# m6502-prototyping-board.net
KiCad netlist of a schematic drawn in EAGLE
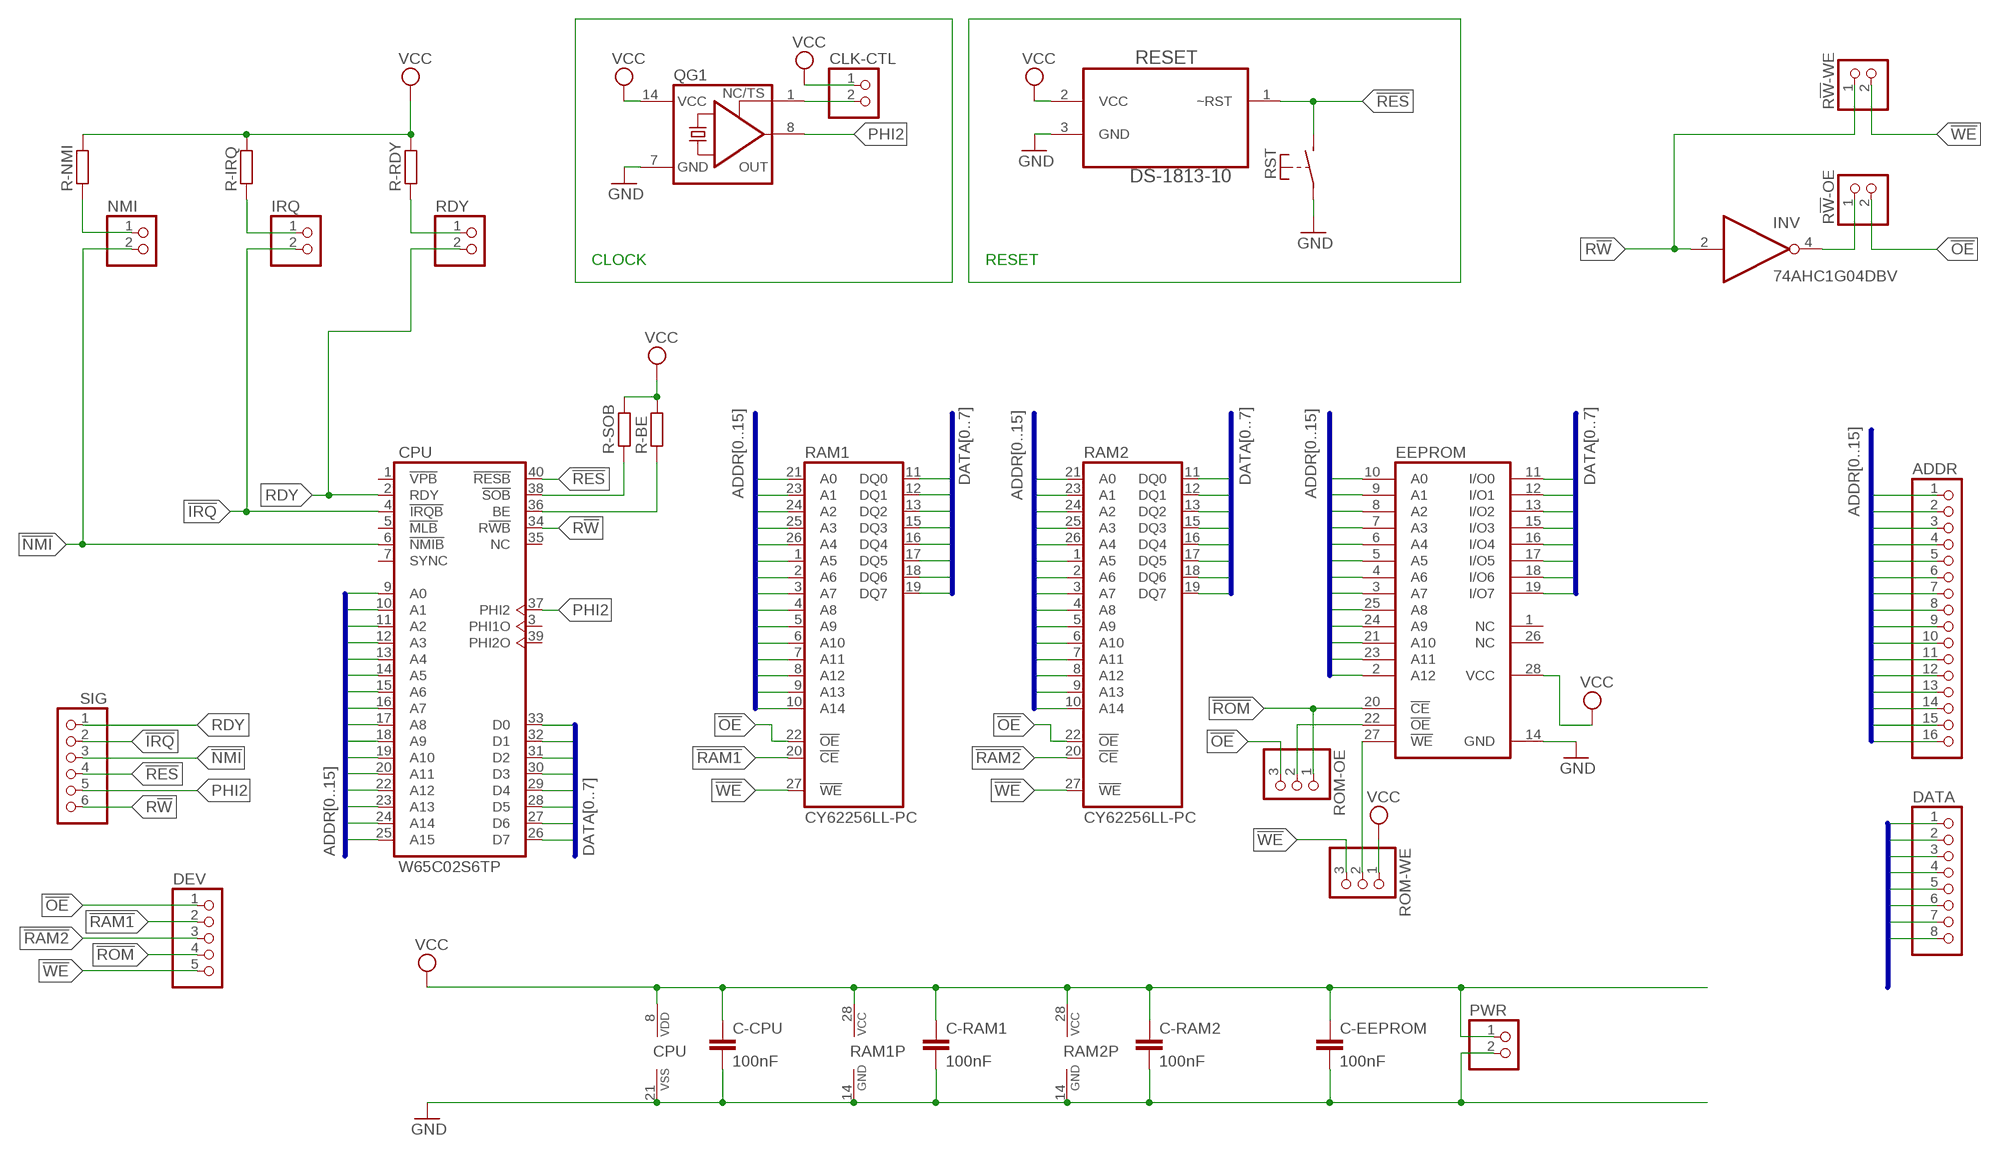
[diagram p0: schematic, sheet 1]

(export (version "E")
  (design (tool "Eeschema 10.0.6"))
  (components
    (comp (ref "ADDR")
      (value "PINHD-1X16")
      (footprint "eagle-import:1X16")
      (libsource (lib "eagle-import") (part "PINHD-1X16"))
    )
    (comp (ref "C-CPU")
      (value "100nF")
      (footprint "eagle-import:C0805")
      (libsource (lib "eagle-import") (part "C-EUC0805"))
    )
    (comp (ref "C-EEPROM")
      (value "100nF")
      (footprint "eagle-import:C0805")
      (libsource (lib "eagle-import") (part "C-EUC0805"))
    )
    (comp (ref "C-RAM1")
      (value "100nF")
      (footprint "eagle-import:C0805")
      (libsource (lib "eagle-import") (part "C-EUC0805"))
    )
    (comp (ref "C-RAM2")
      (value "100nF")
      (footprint "eagle-import:C0805")
      (libsource (lib "eagle-import") (part "C-EUC0805"))
    )
    (comp (ref "CLK-CTL")
      (value "PINHD-1X2")
      (footprint "eagle-import:1X02")
      (libsource (lib "eagle-import") (part "PINHD-1X2"))
    )
    (comp (ref "CPU")
      (value "W65C02S6TP")
      (footprint "eagle-import:DIL40")
      (libsource (lib "eagle-import") (part "W65C02SP6T"))
    )
    (comp (ref "DATA")
      (value "PINHD-1X8")
      (footprint "eagle-import:1X08")
      (libsource (lib "eagle-import") (part "PINHD-1X8"))
    )
    (comp (ref "DEV")
      (value "PINHD-1X5")
      (footprint "eagle-import:1X05")
      (libsource (lib "eagle-import") (part "PINHD-1X5"))
    )
    (comp (ref "EEPROM")
      (value "28C64C")
      (footprint "eagle-import:DIL28-6")
      (fields (field (name "MPN") "AT28C64B-15PU"))
      (libsource (lib "eagle-import") (part "28C64C"))
    )
    (comp (ref "INV")
      (value "74AHC1G04DBV")
      (footprint "eagle-import:SOT23-5")
      (libsource (lib "eagle-import") (part "741G04DBVAHC"))
    )
    (comp (ref "IRQ")
      (value "PINHD-1X2")
      (footprint "eagle-import:1X02")
      (libsource (lib "eagle-import") (part "PINHD-1X2"))
    )
    (comp (ref "NMI")
      (value "PINHD-1X2")
      (footprint "eagle-import:1X02")
      (libsource (lib "eagle-import") (part "PINHD-1X2"))
    )
    (comp (ref "PWR")
      (value "PINHD-1X2")
      (footprint "eagle-import:1X02")
      (libsource (lib "eagle-import") (part "PINHD-1X2"))
    )
    (comp (ref "QG1")
      (value "XO-14")
      (footprint "eagle-import:DIL14S")
      (libsource (lib "eagle-import") (part "XO-14"))
    )
    (comp (ref "R!W!-OE")
      (value "PINHD-1X2")
      (footprint "eagle-import:1X02")
      (libsource (lib "eagle-import") (part "PINHD-1X2"))
    )
    (comp (ref "R!W!-WE")
      (value "PINHD-1X2")
      (footprint "eagle-import:1X02")
      (libsource (lib "eagle-import") (part "PINHD-1X2"))
    )
    (comp (ref "R-BE")
      (value "R-EU_M1206")
      (footprint "eagle-import:M1206")
      (libsource (lib "eagle-import") (part "R-EU_M1206"))
    )
    (comp (ref "R-IRQ")
      (value "R-EU_M1206")
      (footprint "eagle-import:M1206")
      (libsource (lib "eagle-import") (part "R-EU_M1206"))
    )
    (comp (ref "R-NMI")
      (value "R-EU_M1206")
      (footprint "eagle-import:M1206")
      (libsource (lib "eagle-import") (part "R-EU_M1206"))
    )
    (comp (ref "R-RDY")
      (value "R-EU_M1206")
      (footprint "eagle-import:M1206")
      (libsource (lib "eagle-import") (part "R-EU_M1206"))
    )
    (comp (ref "R-SOB")
      (value "R-EU_M1206")
      (footprint "eagle-import:M1206")
      (libsource (lib "eagle-import") (part "R-EU_M1206"))
    )
    (comp (ref "RAM1")
      (value "CY62256LL-PC")
      (footprint "eagle-import:DIL28-6")
      (libsource (lib "eagle-import") (part "CY62256LL-?PC"))
    )
    (comp (ref "RAM2")
      (value "CY62256LL-PC")
      (footprint "eagle-import:DIL28-6")
      (libsource (lib "eagle-import") (part "CY62256LL-?PC"))
    )
    (comp (ref "RDY")
      (value "PINHD-1X2")
      (footprint "eagle-import:1X02")
      (libsource (lib "eagle-import") (part "PINHD-1X2"))
    )
    (comp (ref "RESET")
      (value "DS-1813-10")
      (footprint "eagle-import:TO-92")
      (libsource (lib "eagle-import") (part "DS-1813-10"))
    )
    (comp (ref "ROM-OE")
      (value "PINHD-1X3")
      (footprint "eagle-import:1X03")
      (libsource (lib "eagle-import") (part "PINHD-1X3"))
    )
    (comp (ref "ROM-WE")
      (value "PINHD-1X3")
      (footprint "eagle-import:1X03")
      (libsource (lib "eagle-import") (part "PINHD-1X3"))
    )
    (comp (ref "RST")
      (value "FSM")
      (footprint "eagle-import:FSM")
      (libsource (lib "eagle-import") (part "FSM"))
    )
    (comp (ref "SIG")
      (value "PINHD-1X6")
      (footprint "eagle-import:1X06")
      (libsource (lib "eagle-import") (part "PINHD-1X6"))
    )
  )
  (nets
    (net (code "1") (name "/ADDR0") (class "Default")
      (node (ref "ADDR") (pin "1") (pinfunction "1_1") (pintype "passive"))
      (node (ref "CPU") (pin "9") (pinfunction "A0_9") (pintype "output"))
      (node (ref "EEPROM") (pin "10") (pinfunction "A0_10") (pintype "input"))
      (node (ref "RAM1") (pin "10") (pinfunction "A14_10") (pintype "input"))
      (node (ref "RAM2") (pin "10") (pinfunction "A14_10") (pintype "input"))
    )
    (net (code "2") (name "/ADDR1") (class "Default")
      (node (ref "ADDR") (pin "2") (pinfunction "2_2") (pintype "passive"))
      (node (ref "CPU") (pin "10") (pinfunction "A1_10") (pintype "output"))
      (node (ref "EEPROM") (pin "9") (pinfunction "A1_9") (pintype "input"))
      (node (ref "RAM1") (pin "9") (pinfunction "A13_9") (pintype "input"))
      (node (ref "RAM2") (pin "9") (pinfunction "A13_9") (pintype "input"))
    )
    (net (code "3") (name "/ADDR2") (class "Default")
      (node (ref "ADDR") (pin "3") (pinfunction "3_3") (pintype "passive"))
      (node (ref "CPU") (pin "11") (pinfunction "A2_11") (pintype "output"))
      (node (ref "EEPROM") (pin "8") (pinfunction "A2_8") (pintype "input"))
      (node (ref "RAM1") (pin "8") (pinfunction "A12_8") (pintype "input"))
      (node (ref "RAM2") (pin "8") (pinfunction "A12_8") (pintype "input"))
    )
    (net (code "4") (name "/ADDR3") (class "Default")
      (node (ref "ADDR") (pin "4") (pinfunction "4_4") (pintype "passive"))
      (node (ref "CPU") (pin "12") (pinfunction "A3_12") (pintype "output"))
      (node (ref "EEPROM") (pin "7") (pinfunction "A3_7") (pintype "input"))
      (node (ref "RAM1") (pin "7") (pinfunction "A11_7") (pintype "input"))
      (node (ref "RAM2") (pin "7") (pinfunction "A11_7") (pintype "input"))
    )
    (net (code "5") (name "/ADDR4") (class "Default")
      (node (ref "ADDR") (pin "5") (pinfunction "5_5") (pintype "passive"))
      (node (ref "CPU") (pin "13") (pinfunction "A4_13") (pintype "output"))
      (node (ref "EEPROM") (pin "6") (pinfunction "A4_6") (pintype "input"))
      (node (ref "RAM1") (pin "6") (pinfunction "A10_6") (pintype "input"))
      (node (ref "RAM2") (pin "6") (pinfunction "A10_6") (pintype "input"))
    )
    (net (code "6") (name "/ADDR5") (class "Default")
      (node (ref "ADDR") (pin "6") (pinfunction "6_6") (pintype "passive"))
      (node (ref "CPU") (pin "14") (pinfunction "A5_14") (pintype "output"))
      (node (ref "EEPROM") (pin "5") (pinfunction "A5_5") (pintype "input"))
      (node (ref "RAM1") (pin "5") (pinfunction "A9_5") (pintype "input"))
      (node (ref "RAM2") (pin "5") (pinfunction "A9_5") (pintype "input"))
    )
    (net (code "7") (name "/ADDR6") (class "Default")
      (node (ref "ADDR") (pin "7") (pinfunction "7_7") (pintype "passive"))
      (node (ref "CPU") (pin "15") (pinfunction "A6_15") (pintype "output"))
      (node (ref "EEPROM") (pin "4") (pinfunction "A6_4") (pintype "input"))
      (node (ref "RAM1") (pin "4") (pinfunction "A8_4") (pintype "input"))
      (node (ref "RAM2") (pin "4") (pinfunction "A8_4") (pintype "input"))
    )
    (net (code "8") (name "/ADDR7") (class "Default")
      (node (ref "ADDR") (pin "8") (pinfunction "8_8") (pintype "passive"))
      (node (ref "CPU") (pin "16") (pinfunction "A7_16") (pintype "output"))
      (node (ref "EEPROM") (pin "3") (pinfunction "A7_3") (pintype "input"))
      (node (ref "RAM1") (pin "3") (pinfunction "A7_3") (pintype "input"))
      (node (ref "RAM2") (pin "3") (pinfunction "A7_3") (pintype "input"))
    )
    (net (code "9") (name "/ADDR8") (class "Default")
      (node (ref "ADDR") (pin "9") (pinfunction "9_9") (pintype "passive"))
      (node (ref "CPU") (pin "17") (pinfunction "A8_17") (pintype "output"))
      (node (ref "EEPROM") (pin "25") (pinfunction "A8_25") (pintype "input"))
      (node (ref "RAM1") (pin "25") (pinfunction "A3_25") (pintype "input"))
      (node (ref "RAM2") (pin "25") (pinfunction "A3_25") (pintype "input"))
    )
    (net (code "10") (name "/ADDR9") (class "Default")
      (node (ref "ADDR") (pin "10") (pinfunction "10_10") (pintype "passive"))
      (node (ref "CPU") (pin "18") (pinfunction "A9_18") (pintype "output"))
      (node (ref "EEPROM") (pin "24") (pinfunction "A9_24") (pintype "input"))
      (node (ref "RAM1") (pin "24") (pinfunction "A2_24") (pintype "input"))
      (node (ref "RAM2") (pin "24") (pinfunction "A2_24") (pintype "input"))
    )
    (net (code "11") (name "/ADDR10") (class "Default")
      (node (ref "ADDR") (pin "11") (pinfunction "11_11") (pintype "passive"))
      (node (ref "CPU") (pin "19") (pinfunction "A10_19") (pintype "output"))
      (node (ref "EEPROM") (pin "21") (pinfunction "A10_21") (pintype "input"))
      (node (ref "RAM1") (pin "21") (pinfunction "A0_21") (pintype "input"))
      (node (ref "RAM2") (pin "21") (pinfunction "A0_21") (pintype "input"))
    )
    (net (code "12") (name "/ADDR11") (class "Default")
      (node (ref "ADDR") (pin "12") (pinfunction "12_12") (pintype "passive"))
      (node (ref "CPU") (pin "20") (pinfunction "A11_20") (pintype "output"))
      (node (ref "EEPROM") (pin "23") (pinfunction "A11_23") (pintype "input"))
      (node (ref "RAM1") (pin "23") (pinfunction "A1_23") (pintype "input"))
      (node (ref "RAM2") (pin "23") (pinfunction "A1_23") (pintype "input"))
    )
    (net (code "13") (name "/ADDR12") (class "Default")
      (node (ref "ADDR") (pin "13") (pinfunction "13_13") (pintype "passive"))
      (node (ref "CPU") (pin "22") (pinfunction "A12_22") (pintype "output"))
      (node (ref "EEPROM") (pin "2") (pinfunction "A12_2") (pintype "input"))
      (node (ref "RAM1") (pin "2") (pinfunction "A6_2") (pintype "input"))
      (node (ref "RAM2") (pin "2") (pinfunction "A6_2") (pintype "input"))
    )
    (net (code "14") (name "/ADDR13") (class "Default")
      (node (ref "ADDR") (pin "14") (pinfunction "14_14") (pintype "passive"))
      (node (ref "CPU") (pin "23") (pinfunction "A13_23") (pintype "output"))
      (node (ref "RAM1") (pin "26") (pinfunction "A4_26") (pintype "input"))
      (node (ref "RAM2") (pin "26") (pinfunction "A4_26") (pintype "input"))
    )
    (net (code "15") (name "/ADDR14") (class "Default")
      (node (ref "ADDR") (pin "15") (pinfunction "15_15") (pintype "passive"))
      (node (ref "CPU") (pin "24") (pinfunction "A14_24") (pintype "output"))
      (node (ref "RAM1") (pin "1") (pinfunction "A5_1") (pintype "input"))
      (node (ref "RAM2") (pin "1") (pinfunction "A5_1") (pintype "input"))
    )
    (net (code "16") (name "/ADDR15") (class "Default")
      (node (ref "ADDR") (pin "16") (pinfunction "16_16") (pintype "passive"))
      (node (ref "CPU") (pin "25") (pinfunction "A15_25") (pintype "output"))
    )
    (net (code "18") (name "/DATA0") (class "Default")
      (node (ref "CPU") (pin "33") (pinfunction "D0_33") (pintype "bidirectional"))
      (node (ref "DATA") (pin "1") (pinfunction "1_1") (pintype "passive"))
      (node (ref "EEPROM") (pin "11") (pinfunction "I/O0_11") (pintype "bidirectional"))
      (node (ref "RAM1") (pin "11") (pinfunction "DQ0_11") (pintype "bidirectional"))
      (node (ref "RAM2") (pin "11") (pinfunction "DQ0_11") (pintype "bidirectional"))
    )
    (net (code "19") (name "/DATA1") (class "Default")
      (node (ref "CPU") (pin "32") (pinfunction "D1_32") (pintype "bidirectional"))
      (node (ref "DATA") (pin "2") (pinfunction "2_2") (pintype "passive"))
      (node (ref "EEPROM") (pin "12") (pinfunction "I/O1_12") (pintype "bidirectional"))
      (node (ref "RAM1") (pin "12") (pinfunction "DQ1_12") (pintype "bidirectional"))
      (node (ref "RAM2") (pin "12") (pinfunction "DQ1_12") (pintype "bidirectional"))
    )
    (net (code "20") (name "/DATA2") (class "Default")
      (node (ref "CPU") (pin "31") (pinfunction "D2_31") (pintype "bidirectional"))
      (node (ref "DATA") (pin "3") (pinfunction "3_3") (pintype "passive"))
      (node (ref "EEPROM") (pin "13") (pinfunction "I/O2_13") (pintype "bidirectional"))
      (node (ref "RAM1") (pin "13") (pinfunction "DQ2_13") (pintype "bidirectional"))
      (node (ref "RAM2") (pin "13") (pinfunction "DQ2_13") (pintype "bidirectional"))
    )
    (net (code "21") (name "/DATA3") (class "Default")
      (node (ref "CPU") (pin "30") (pinfunction "D3_30") (pintype "bidirectional"))
      (node (ref "DATA") (pin "4") (pinfunction "4_4") (pintype "passive"))
      (node (ref "EEPROM") (pin "15") (pinfunction "I/O3_15") (pintype "bidirectional"))
      (node (ref "RAM1") (pin "15") (pinfunction "DQ3_15") (pintype "bidirectional"))
      (node (ref "RAM2") (pin "15") (pinfunction "DQ3_15") (pintype "bidirectional"))
    )
    (net (code "22") (name "/DATA4") (class "Default")
      (node (ref "CPU") (pin "29") (pinfunction "D4_29") (pintype "bidirectional"))
      (node (ref "DATA") (pin "5") (pinfunction "5_5") (pintype "passive"))
      (node (ref "EEPROM") (pin "16") (pinfunction "I/O4_16") (pintype "bidirectional"))
      (node (ref "RAM1") (pin "16") (pinfunction "DQ4_16") (pintype "bidirectional"))
      (node (ref "RAM2") (pin "16") (pinfunction "DQ4_16") (pintype "bidirectional"))
    )
    (net (code "23") (name "/DATA5") (class "Default")
      (node (ref "CPU") (pin "28") (pinfunction "D5_28") (pintype "bidirectional"))
      (node (ref "DATA") (pin "6") (pinfunction "6_6") (pintype "passive"))
      (node (ref "EEPROM") (pin "17") (pinfunction "I/O5_17") (pintype "bidirectional"))
      (node (ref "RAM1") (pin "17") (pinfunction "DQ5_17") (pintype "bidirectional"))
      (node (ref "RAM2") (pin "17") (pinfunction "DQ5_17") (pintype "bidirectional"))
    )
    (net (code "24") (name "/DATA6") (class "Default")
      (node (ref "CPU") (pin "27") (pinfunction "D6_27") (pintype "bidirectional"))
      (node (ref "DATA") (pin "7") (pinfunction "7_7") (pintype "passive"))
      (node (ref "EEPROM") (pin "18") (pinfunction "I/O6_18") (pintype "bidirectional"))
      (node (ref "RAM1") (pin "18") (pinfunction "DQ6_18") (pintype "bidirectional"))
      (node (ref "RAM2") (pin "18") (pinfunction "DQ6_18") (pintype "bidirectional"))
    )
    (net (code "25") (name "/DATA7") (class "Default")
      (node (ref "CPU") (pin "26") (pinfunction "D7_26") (pintype "bidirectional"))
      (node (ref "DATA") (pin "8") (pinfunction "8_8") (pintype "passive"))
      (node (ref "EEPROM") (pin "19") (pinfunction "I/O7_19") (pintype "bidirectional"))
      (node (ref "RAM1") (pin "19") (pinfunction "DQ7_19") (pintype "bidirectional"))
      (node (ref "RAM2") (pin "19") (pinfunction "DQ7_19") (pintype "bidirectional"))
    )
    (net (code "27") (name "/R~{W}") (class "Default")
      (node (ref "CPU") (pin "34") (pinfunction "R~{WB}_34") (pintype "output"))
      (node (ref "INV") (pin "2") (pinfunction "I_2") (pintype "input"))
      (node (ref "R!W!-WE") (pin "1") (pinfunction "1_1") (pintype "passive"))
      (node (ref "SIG") (pin "6") (pinfunction "6_6") (pintype "passive"))
    )
    (net (code "28") (name "/~{IRQ}") (class "Default")
      (node (ref "CPU") (pin "4") (pinfunction "~{IRQB}_4") (pintype "input"))
      (node (ref "IRQ") (pin "2") (pinfunction "2_2") (pintype "passive"))
      (node (ref "SIG") (pin "2") (pinfunction "2_2") (pintype "passive"))
    )
    (net (code "29") (name "/~{NMI}") (class "Default")
      (node (ref "CPU") (pin "6") (pinfunction "~{NMIB}_6") (pintype "input"))
      (node (ref "NMI") (pin "2") (pinfunction "2_2") (pintype "passive"))
      (node (ref "SIG") (pin "3") (pinfunction "3_3") (pintype "passive"))
    )
    (net (code "30") (name "/~{OE}") (class "Default")
      (node (ref "DEV") (pin "1") (pinfunction "1_1") (pintype "passive"))
      (node (ref "R!W!-OE") (pin "2") (pinfunction "2_2") (pintype "passive"))
      (node (ref "RAM1") (pin "22") (pinfunction "~{OE}_22") (pintype "input"))
      (node (ref "RAM2") (pin "22") (pinfunction "~{OE}_22") (pintype "input"))
      (node (ref "ROM-OE") (pin "3") (pinfunction "3_3") (pintype "passive"))
    )
    (net (code "31") (name "/~{RAM1}") (class "Default")
      (node (ref "DEV") (pin "2") (pinfunction "2_2") (pintype "passive"))
      (node (ref "RAM1") (pin "20") (pinfunction "~{CE}_20") (pintype "input"))
    )
    (net (code "32") (name "/~{RAM2}") (class "Default")
      (node (ref "DEV") (pin "3") (pinfunction "3_3") (pintype "passive"))
      (node (ref "RAM2") (pin "20") (pinfunction "~{CE}_20") (pintype "input"))
    )
    (net (code "33") (name "/~{RES}") (class "Default")
      (node (ref "CPU") (pin "40") (pinfunction "~{RESB}_40") (pintype "input"))
      (node (ref "RESET") (pin "1") (pinfunction "~{RST}_1") (pintype "output"))
      (node (ref "RST") (pin "P$2") (pinfunction "S_P$2") (pintype "passive"))
      (node (ref "SIG") (pin "4") (pinfunction "4_4") (pintype "passive"))
    )
    (net (code "34") (name "/~{ROM}") (class "Default")
      (node (ref "DEV") (pin "4") (pinfunction "4_4") (pintype "passive"))
      (node (ref "EEPROM") (pin "20") (pinfunction "~{CE}_20") (pintype "input"))
      (node (ref "ROM-OE") (pin "1") (pinfunction "1_1") (pintype "passive"))
    )
    (net (code "35") (name "/~{WE}") (class "Default")
      (node (ref "DEV") (pin "5") (pinfunction "5_5") (pintype "passive"))
      (node (ref "R!W!-WE") (pin "2") (pinfunction "2_2") (pintype "passive"))
      (node (ref "RAM1") (pin "27") (pinfunction "~{WE}_27") (pintype "input"))
      (node (ref "RAM2") (pin "27") (pinfunction "~{WE}_27") (pintype "input"))
      (node (ref "ROM-WE") (pin "3") (pinfunction "3_3") (pintype "passive"))
    )
    (net (code "36") (name "GND") (class "Default")
      (node (ref "C-CPU") (pin "2") (pinfunction "2_2") (pintype "passive"))
      (node (ref "C-EEPROM") (pin "2") (pinfunction "2_2") (pintype "passive"))
      (node (ref "C-RAM1") (pin "2") (pinfunction "2_2") (pintype "passive"))
      (node (ref "C-RAM2") (pin "2") (pinfunction "2_2") (pintype "passive"))
      (node (ref "CPU") (pin "21") (pinfunction "VSS_21") (pintype "power_in"))
      (node (ref "EEPROM") (pin "14") (pinfunction "GND_14") (pintype "power_in"))
      (node (ref "PWR") (pin "2") (pinfunction "2_2") (pintype "passive"))
      (node (ref "QG1") (pin "7") (pinfunction "GND_7") (pintype "power_in"))
      (node (ref "RAM1") (pin "14") (pinfunction "GND_14") (pintype "power_in"))
      (node (ref "RAM2") (pin "14") (pinfunction "GND_14") (pintype "power_in"))
      (node (ref "RESET") (pin "3") (pinfunction "GND_3") (pintype "passive"))
      (node (ref "RST") (pin "P$1") (pinfunction "P_P$1") (pintype "passive"))
    )
    (net (code "37") (name "Net-(CPUA-BE)") (class "Default")
      (node (ref "CPU") (pin "36") (pinfunction "BE_36") (pintype "input"))
      (node (ref "R-BE") (pin "1") (pinfunction "1_1") (pintype "passive"))
    )
    (net (code "38") (name "Net-(CPUA-~{SOB})") (class "Default")
      (node (ref "CPU") (pin "38") (pinfunction "~{SOB}_38") (pintype "input"))
      (node (ref "R-SOB") (pin "1") (pinfunction "1_1") (pintype "passive"))
    )
    (net (code "39") (name "Net-(EEPROM-~{OE})") (class "Default")
      (node (ref "EEPROM") (pin "22") (pinfunction "~{OE}_22") (pintype "input"))
      (node (ref "ROM-OE") (pin "2") (pinfunction "2_2") (pintype "passive"))
    )
    (net (code "40") (name "Net-(EEPROM-~{WE})") (class "Default")
      (node (ref "EEPROM") (pin "27") (pinfunction "~{WE}_27") (pintype "input"))
      (node (ref "ROM-WE") (pin "2") (pinfunction "2_2") (pintype "passive"))
    )
    (net (code "41") (name "Net-(INVA-O)") (class "Default")
      (node (ref "INV") (pin "4") (pinfunction "O_4") (pintype "output"))
      (node (ref "R!W!-OE") (pin "1") (pinfunction "1_1") (pintype "passive"))
    )
    (net (code "42") (name "Net-(IRQ-Pad1)") (class "Default")
      (node (ref "IRQ") (pin "1") (pinfunction "1_1") (pintype "passive"))
      (node (ref "R-IRQ") (pin "1") (pinfunction "1_1") (pintype "passive"))
    )
    (net (code "43") (name "Net-(NMI-Pad1)") (class "Default")
      (node (ref "NMI") (pin "1") (pinfunction "1_1") (pintype "passive"))
      (node (ref "R-NMI") (pin "1") (pinfunction "1_1") (pintype "passive"))
    )
    (net (code "44") (name "Net-(QG1-TS)") (class "Default")
      (node (ref "CLK-CTL") (pin "2") (pinfunction "2_2") (pintype "passive"))
      (node (ref "QG1") (pin "1") (pinfunction "TS_1") (pintype "passive"))
    )
    (net (code "45") (name "Net-(R-RDY-Pad1)") (class "Default")
      (node (ref "R-RDY") (pin "1") (pinfunction "1_1") (pintype "passive"))
      (node (ref "RDY") (pin "1") (pinfunction "1_1") (pintype "passive"))
    )
    (net (code "46") (name "PHI2") (class "Default")
      (node (ref "CPU") (pin "37") (pinfunction "PHI2_37") (pintype "input"))
      (node (ref "QG1") (pin "8") (pinfunction "OUT_8") (pintype "output"))
      (node (ref "SIG") (pin "5") (pinfunction "5_5") (pintype "passive"))
    )
    (net (code "47") (name "RDY") (class "Default")
      (node (ref "CPU") (pin "2") (pinfunction "RDY_2") (pintype "input"))
      (node (ref "RDY") (pin "2") (pinfunction "2_2") (pintype "passive"))
      (node (ref "SIG") (pin "1") (pinfunction "1_1") (pintype "passive"))
    )
    (net (code "48") (name "VCC") (class "Default")
      (node (ref "C-CPU") (pin "1") (pinfunction "1_1") (pintype "passive"))
      (node (ref "C-EEPROM") (pin "1") (pinfunction "1_1") (pintype "passive"))
      (node (ref "C-RAM1") (pin "1") (pinfunction "1_1") (pintype "passive"))
      (node (ref "C-RAM2") (pin "1") (pinfunction "1_1") (pintype "passive"))
      (node (ref "CLK-CTL") (pin "1") (pinfunction "1_1") (pintype "passive"))
      (node (ref "CPU") (pin "8") (pinfunction "VDD_8") (pintype "power_in"))
      (node (ref "EEPROM") (pin "28") (pinfunction "VCC_28") (pintype "power_in"))
      (node (ref "PWR") (pin "1") (pinfunction "1_1") (pintype "passive"))
      (node (ref "QG1") (pin "14") (pinfunction "VCC_14") (pintype "power_in"))
      (node (ref "R-BE") (pin "2") (pinfunction "2_2") (pintype "passive"))
      (node (ref "R-IRQ") (pin "2") (pinfunction "2_2") (pintype "passive"))
      (node (ref "R-NMI") (pin "2") (pinfunction "2_2") (pintype "passive"))
      (node (ref "R-RDY") (pin "2") (pinfunction "2_2") (pintype "passive"))
      (node (ref "R-SOB") (pin "2") (pinfunction "2_2") (pintype "passive"))
      (node (ref "RAM1") (pin "28") (pinfunction "VCC_28") (pintype "power_in"))
      (node (ref "RAM2") (pin "28") (pinfunction "VCC_28") (pintype "power_in"))
      (node (ref "RESET") (pin "2") (pinfunction "VCC_2") (pintype "power_in"))
      (node (ref "ROM-WE") (pin "1") (pinfunction "1_1") (pintype "passive"))
    )
    (net (code "49") (name "unconnected-(CPUA-NC-Pad35)") (class "Default")
      (node (ref "CPU") (pin "35") (pinfunction "NC_35") (pintype "no_connect"))
    )
    (net (code "50") (name "unconnected-(CPUA-PHI1O-Pad3)") (class "Default")
      (node (ref "CPU") (pin "3") (pinfunction "PHI1O_3") (pintype "output"))
    )
    (net (code "51") (name "unconnected-(CPUA-PHI2O-Pad39)") (class "Default")
      (node (ref "CPU") (pin "39") (pinfunction "PHI2O_39") (pintype "output"))
    )
    (net (code "52") (name "unconnected-(CPUA-SYNC-Pad7)") (class "Default")
      (node (ref "CPU") (pin "7") (pinfunction "SYNC_7") (pintype "output"))
    )
    (net (code "53") (name "unconnected-(CPUA-~{MLB}-Pad5)") (class "Default")
      (node (ref "CPU") (pin "5") (pinfunction "~{MLB}_5") (pintype "output"))
    )
    (net (code "54") (name "unconnected-(CPUA-~{VPB}-Pad1)") (class "Default")
      (node (ref "CPU") (pin "1") (pinfunction "~{VPB}_1") (pintype "output"))
    )
    (net (code "55") (name "unconnected-(EEPROM-NC-Pad1)") (class "Default")
      (node (ref "EEPROM") (pin "1") (pinfunction "NC_1") (pintype "no_connect"))
    )
    (net (code "56") (name "unconnected-(EEPROM-NC-Pad26)") (class "Default")
      (node (ref "EEPROM") (pin "26") (pinfunction "NC_26") (pintype "no_connect"))
    )
  )
)
